# pic32john.net
KiCad netlist of a schematic drawn in EAGLE
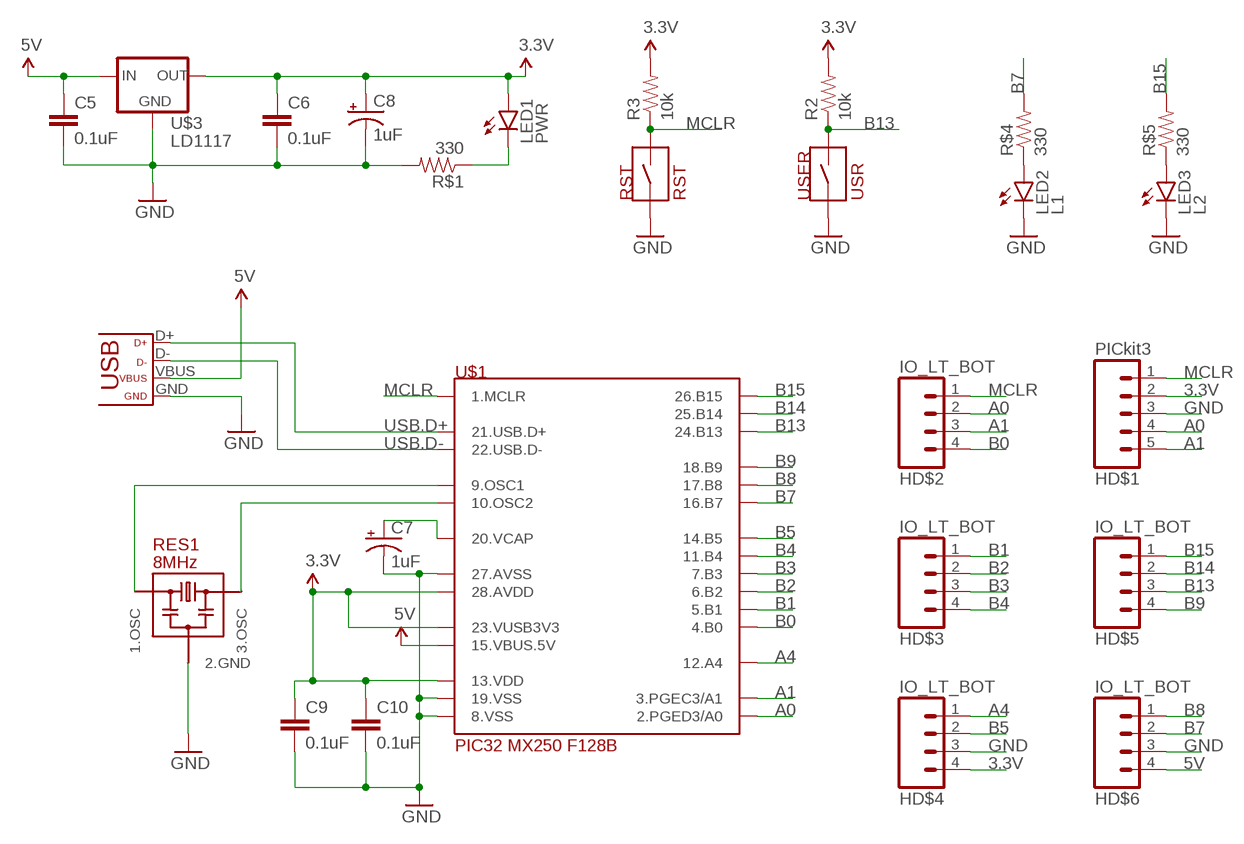
[diagram p0: schematic, sheet 1]

(export (version "E")
  (design (tool "Eeschema 10.0.6"))
  (components
    (comp (ref "C5")
      (value "0.1uF")
      (footprint "eagle-import:CAP-PTH-SMALL")
      (libsource (lib "eagle-import") (part "CAPPTH"))
    )
    (comp (ref "C6")
      (value "0.1uF")
      (footprint "eagle-import:CAP-PTH-SMALL")
      (libsource (lib "eagle-import") (part "CAPPTH"))
    )
    (comp (ref "C7")
      (value "1uF")
      (footprint "eagle-import:CPOL-RADIAL-10UF-25V")
      (libsource (lib "eagle-import") (part "CAP_POLPTH2"))
    )
    (comp (ref "C8")
      (value "1uF")
      (footprint "eagle-import:CPOL-RADIAL-10UF-25V")
      (libsource (lib "eagle-import") (part "CAP_POLPTH2"))
    )
    (comp (ref "C9")
      (value "0.1uF")
      (footprint "eagle-import:CAP-PTH-SMALL")
      (libsource (lib "eagle-import") (part "CAPPTH"))
    )
    (comp (ref "C10")
      (value "0.1uF")
      (footprint "eagle-import:CAP-PTH-SMALL")
      (libsource (lib "eagle-import") (part "CAPPTH"))
    )
    (comp (ref "HD$1")
      (value "PICkit3")
      (footprint "eagle-import:1X05")
      (libsource (lib "eagle-import") (part "M05PTH"))
    )
    (comp (ref "HD$2")
      (value "IO_LT_BOT")
      (footprint "eagle-import:1X04")
      (libsource (lib "eagle-import") (part "M04PTH"))
    )
    (comp (ref "HD$3")
      (value "IO_LT_BOT")
      (footprint "eagle-import:1X04")
      (libsource (lib "eagle-import") (part "M04PTH"))
    )
    (comp (ref "HD$4")
      (value "IO_LT_BOT")
      (footprint "eagle-import:1X04")
      (libsource (lib "eagle-import") (part "M04PTH"))
    )
    (comp (ref "HD$5")
      (value "IO_LT_BOT")
      (footprint "eagle-import:1X04")
      (libsource (lib "eagle-import") (part "M04PTH"))
    )
    (comp (ref "HD$6")
      (value "IO_LT_BOT")
      (footprint "eagle-import:1X04")
      (libsource (lib "eagle-import") (part "M04PTH"))
    )
    (comp (ref "LED1")
      (value "PWR")
      (footprint "eagle-import:LED3MM")
      (libsource (lib "eagle-import") (part "LED3MM"))
    )
    (comp (ref "LED2")
      (value "L1")
      (footprint "eagle-import:LED3MM")
      (libsource (lib "eagle-import") (part "LED3MM"))
    )
    (comp (ref "LED3")
      (value "L2")
      (footprint "eagle-import:LED3MM")
      (libsource (lib "eagle-import") (part "LED3MM"))
    )
    (comp (ref "R$1")
      (value "330")
      (footprint "eagle-import:AXIAL-0.4")
      (libsource (lib "eagle-import") (part "RESISTORPTH-1/4W"))
    )
    (comp (ref "R$4")
      (value "330")
      (footprint "eagle-import:AXIAL-0.4")
      (libsource (lib "eagle-import") (part "RESISTORPTH-1/4W"))
    )
    (comp (ref "R$5")
      (value "330")
      (footprint "eagle-import:AXIAL-0.4")
      (libsource (lib "eagle-import") (part "RESISTORPTH-1/4W"))
    )
    (comp (ref "R2")
      (value "10k")
      (footprint "eagle-import:AXIAL-0.4")
      (libsource (lib "eagle-import") (part "RESISTORPTH-1/4W"))
    )
    (comp (ref "R3")
      (value "10k")
      (footprint "eagle-import:AXIAL-0.4")
      (libsource (lib "eagle-import") (part "RESISTORPTH-1/4W"))
    )
    (comp (ref "RES1")
      (value "8MHz")
      (footprint "eagle-import:RESONATOR_PTH")
      (libsource (lib "eagle-import") (part "RESONATOR"))
    )
    (comp (ref "RST")
      (value "RST")
      (footprint "eagle-import:BTN_P8072")
      (libsource (lib "eagle-import") (part "BTN_P8072"))
    )
    (comp (ref "U$1")
      (value "PIC32MX250F128B")
      (footprint "eagle-import:DIL_28_3_JOHN")
      (libsource (lib "eagle-import") (part "PIC32MX250F128B"))
    )
    (comp (ref "U$2")
      (value "USB")
      (footprint "eagle-import:USB-MINIB")
      (libsource (lib "eagle-import") (part "USB"))
    )
    (comp (ref "U$3")
      (value "LD1117")
      (footprint "eagle-import:TO220")
      (libsource (lib "eagle-import") (part "LD1117"))
    )
    (comp (ref "USER")
      (value "USR")
      (footprint "eagle-import:BTN_P8072")
      (libsource (lib "eagle-import") (part "BTN_P8072"))
    )
  )
  (nets
    (net (code "1") (name "/A0") (class "Default")
      (node (ref "HD$1") (pin "4") (pinfunction "4_4") (pintype "passive"))
      (node (ref "HD$2") (pin "2") (pinfunction "2_2") (pintype "passive"))
      (node (ref "U$1") (pin "P$2") (pinfunction "2.PGED3/A0_P$2") (pintype "bidirectional"))
    )
    (net (code "2") (name "/A1") (class "Default")
      (node (ref "HD$1") (pin "5") (pinfunction "5_5") (pintype "passive"))
      (node (ref "HD$2") (pin "3") (pinfunction "3_3") (pintype "passive"))
      (node (ref "U$1") (pin "P$3") (pinfunction "3.PGEC3/A1_P$3") (pintype "bidirectional"))
    )
    (net (code "3") (name "/A4") (class "Default")
      (node (ref "HD$4") (pin "1") (pinfunction "1_1") (pintype "passive"))
      (node (ref "U$1") (pin "P$12") (pinfunction "12.A4_P$12") (pintype "bidirectional"))
    )
    (net (code "4") (name "/B0") (class "Default")
      (node (ref "HD$2") (pin "4") (pinfunction "4_4") (pintype "passive"))
      (node (ref "U$1") (pin "P$4") (pinfunction "4.B0_P$4") (pintype "bidirectional"))
    )
    (net (code "5") (name "/B1") (class "Default")
      (node (ref "HD$3") (pin "1") (pinfunction "1_1") (pintype "passive"))
      (node (ref "U$1") (pin "P$5") (pinfunction "5.B1_P$5") (pintype "bidirectional"))
    )
    (net (code "6") (name "/B2") (class "Default")
      (node (ref "HD$3") (pin "2") (pinfunction "2_2") (pintype "passive"))
      (node (ref "U$1") (pin "P$6") (pinfunction "6.B2_P$6") (pintype "bidirectional"))
    )
    (net (code "7") (name "/B3") (class "Default")
      (node (ref "HD$3") (pin "3") (pinfunction "3_3") (pintype "passive"))
      (node (ref "U$1") (pin "P$7") (pinfunction "7.B3_P$7") (pintype "bidirectional"))
    )
    (net (code "8") (name "/B4") (class "Default")
      (node (ref "HD$3") (pin "4") (pinfunction "4_4") (pintype "passive"))
      (node (ref "U$1") (pin "P$11") (pinfunction "11.B4_P$11") (pintype "bidirectional"))
    )
    (net (code "9") (name "/B5") (class "Default")
      (node (ref "HD$4") (pin "2") (pinfunction "2_2") (pintype "passive"))
      (node (ref "U$1") (pin "P$14") (pinfunction "14.B5_P$14") (pintype "bidirectional"))
    )
    (net (code "10") (name "/B7") (class "Default")
      (node (ref "HD$6") (pin "2") (pinfunction "2_2") (pintype "passive"))
      (node (ref "R$4") (pin "P$2") (pinfunction "2_P$2") (pintype "passive"))
      (node (ref "U$1") (pin "P$16") (pinfunction "16.B7_P$16") (pintype "bidirectional"))
    )
    (net (code "11") (name "/B8") (class "Default")
      (node (ref "HD$6") (pin "1") (pinfunction "1_1") (pintype "passive"))
      (node (ref "U$1") (pin "P$17") (pinfunction "17.B8_P$17") (pintype "bidirectional"))
    )
    (net (code "12") (name "/B9") (class "Default")
      (node (ref "HD$5") (pin "4") (pinfunction "4_4") (pintype "passive"))
      (node (ref "U$1") (pin "P$18") (pinfunction "18.B9_P$18") (pintype "bidirectional"))
    )
    (net (code "13") (name "/B13") (class "Default")
      (node (ref "HD$5") (pin "3") (pinfunction "3_3") (pintype "passive"))
      (node (ref "R2") (pin "P$1") (pinfunction "1_P$1") (pintype "passive"))
      (node (ref "U$1") (pin "P$24") (pinfunction "24.B13_P$24") (pintype "bidirectional"))
      (node (ref "USER") (pin "P$2") (pinfunction "P$2_P$2") (pintype "bidirectional"))
    )
    (net (code "14") (name "/B14") (class "Default")
      (node (ref "HD$5") (pin "2") (pinfunction "2_2") (pintype "passive"))
      (node (ref "U$1") (pin "P$25") (pinfunction "25.B14_P$25") (pintype "bidirectional"))
    )
    (net (code "15") (name "/B15") (class "Default")
      (node (ref "HD$5") (pin "1") (pinfunction "1_1") (pintype "passive"))
      (node (ref "R$5") (pin "P$2") (pinfunction "2_P$2") (pintype "passive"))
      (node (ref "U$1") (pin "P$26") (pinfunction "26.B15_P$26") (pintype "bidirectional"))
    )
    (net (code "16") (name "/MCLR") (class "Default")
      (node (ref "HD$1") (pin "1") (pinfunction "1_1") (pintype "passive"))
      (node (ref "HD$2") (pin "1") (pinfunction "1_1") (pintype "passive"))
      (node (ref "R3") (pin "P$1") (pinfunction "1_P$1") (pintype "passive"))
      (node (ref "RST") (pin "P$2") (pinfunction "P$2_P$2") (pintype "bidirectional"))
      (node (ref "U$1") (pin "P$1") (pinfunction "1.MCLR_P$1") (pintype "input"))
    )
    (net (code "17") (name "/USB.D+") (class "Default")
      (node (ref "U$1") (pin "P$21") (pinfunction "21.USB.D+_P$21") (pintype "bidirectional"))
      (node (ref "U$2") (pin "D+") (pinfunction "D+_D+") (pintype "bidirectional"))
    )
    (net (code "18") (name "/USB.D-") (class "Default")
      (node (ref "U$1") (pin "P$22") (pinfunction "22.USB.D-_P$22") (pintype "bidirectional"))
      (node (ref "U$2") (pin "D-") (pinfunction "D-_D-") (pintype "bidirectional"))
    )
    (net (code "19") (name "3.3V") (class "Default")
      (node (ref "C10") (pin "1") (pinfunction "1_1") (pintype "passive"))
      (node (ref "C6") (pin "1") (pinfunction "1_1") (pintype "passive"))
      (node (ref "C8") (pin "1") (pinfunction "+_1") (pintype "passive"))
      (node (ref "C9") (pin "1") (pinfunction "1_1") (pintype "passive"))
      (node (ref "HD$1") (pin "2") (pinfunction "2_2") (pintype "passive"))
      (node (ref "HD$4") (pin "4") (pinfunction "4_4") (pintype "passive"))
      (node (ref "LED1") (pin "A") (pinfunction "A_A") (pintype "passive"))
      (node (ref "R2") (pin "P$2") (pinfunction "2_P$2") (pintype "passive"))
      (node (ref "R3") (pin "P$2") (pinfunction "2_P$2") (pintype "passive"))
      (node (ref "U$1") (pin "P$13") (pinfunction "13.VDD_P$13") (pintype "power_in"))
      (node (ref "U$1") (pin "P$23") (pinfunction "23.VUSB3V3_P$23") (pintype "power_in"))
      (node (ref "U$1") (pin "P$28") (pinfunction "28.AVDD_P$28") (pintype "power_in"))
      (node (ref "U$3") (pin "2") (pinfunction "OUT_2") (pintype "output"))
    )
    (net (code "20") (name "5V") (class "Default")
      (node (ref "C5") (pin "1") (pinfunction "1_1") (pintype "passive"))
      (node (ref "HD$6") (pin "4") (pinfunction "4_4") (pintype "passive"))
      (node (ref "U$1") (pin "P$15") (pinfunction "15.VBUS.5V_P$15") (pintype "power_in"))
      (node (ref "U$2") (pin "VBUS") (pinfunction "VBUS_VBUS") (pintype "bidirectional"))
      (node (ref "U$3") (pin "3") (pinfunction "IN_3") (pintype "input"))
    )
    (net (code "21") (name "GND") (class "Default")
      (node (ref "C10") (pin "2") (pinfunction "2_2") (pintype "passive"))
      (node (ref "C5") (pin "2") (pinfunction "2_2") (pintype "passive"))
      (node (ref "C6") (pin "2") (pinfunction "2_2") (pintype "passive"))
      (node (ref "C7") (pin "2") (pinfunction "-_2") (pintype "passive"))
      (node (ref "C8") (pin "2") (pinfunction "-_2") (pintype "passive"))
      (node (ref "C9") (pin "2") (pinfunction "2_2") (pintype "passive"))
      (node (ref "HD$1") (pin "3") (pinfunction "3_3") (pintype "passive"))
      (node (ref "HD$4") (pin "3") (pinfunction "3_3") (pintype "passive"))
      (node (ref "HD$6") (pin "3") (pinfunction "3_3") (pintype "passive"))
      (node (ref "LED2") (pin "K") (pinfunction "C_K") (pintype "passive"))
      (node (ref "LED3") (pin "K") (pinfunction "C_K") (pintype "passive"))
      (node (ref "R$1") (pin "P$2") (pinfunction "2_P$2") (pintype "passive"))
      (node (ref "RES1") (pin "P$2") (pinfunction "2.GND_P$2") (pintype "power_in"))
      (node (ref "RST") (pin "P$1") (pinfunction "P$1_P$1") (pintype "bidirectional"))
      (node (ref "U$1") (pin "P$19") (pinfunction "19.VSS_P$19") (pintype "power_in"))
      (node (ref "U$1") (pin "P$27") (pinfunction "27.AVSS_P$27") (pintype "power_in"))
      (node (ref "U$1") (pin "P$8") (pinfunction "8.VSS_P$8") (pintype "power_in"))
      (node (ref "U$2") (pin "GND") (pinfunction "GND_GND") (pintype "bidirectional"))
      (node (ref "U$3") (pin "1") (pinfunction "GND_1") (pintype "input"))
      (node (ref "USER") (pin "P$1") (pinfunction "P$1_P$1") (pintype "bidirectional"))
    )
    (net (code "22") (name "Net-(C7-+)") (class "Default")
      (node (ref "C7") (pin "1") (pinfunction "+_1") (pintype "passive"))
      (node (ref "U$1") (pin "P$20") (pinfunction "20.VCAP_P$20") (pintype "power_in"))
    )
    (net (code "23") (name "Net-(LED1-C)") (class "Default")
      (node (ref "LED1") (pin "K") (pinfunction "C_K") (pintype "passive"))
      (node (ref "R$1") (pin "P$1") (pinfunction "1_P$1") (pintype "passive"))
    )
    (net (code "24") (name "Net-(R$4-1)") (class "Default")
      (node (ref "LED2") (pin "A") (pinfunction "A_A") (pintype "passive"))
      (node (ref "R$4") (pin "P$1") (pinfunction "1_P$1") (pintype "passive"))
    )
    (net (code "25") (name "Net-(R$5-1)") (class "Default")
      (node (ref "LED3") (pin "A") (pinfunction "A_A") (pintype "passive"))
      (node (ref "R$5") (pin "P$1") (pinfunction "1_P$1") (pintype "passive"))
    )
    (net (code "26") (name "Net-(RES1-1.OSC)") (class "Default")
      (node (ref "RES1") (pin "P$3") (pinfunction "1.OSC_P$3") (pintype "bidirectional"))
      (node (ref "U$1") (pin "P$9") (pinfunction "9.OSC1_P$9") (pintype "input"))
    )
    (net (code "27") (name "Net-(RES1-3.OSC)") (class "Default")
      (node (ref "RES1") (pin "P$1") (pinfunction "3.OSC_P$1") (pintype "bidirectional"))
      (node (ref "U$1") (pin "P$10") (pinfunction "10.OSC2_P$10") (pintype "input"))
    )
  )
)
